# me433.net
KiCad netlist of a schematic drawn in EAGLE
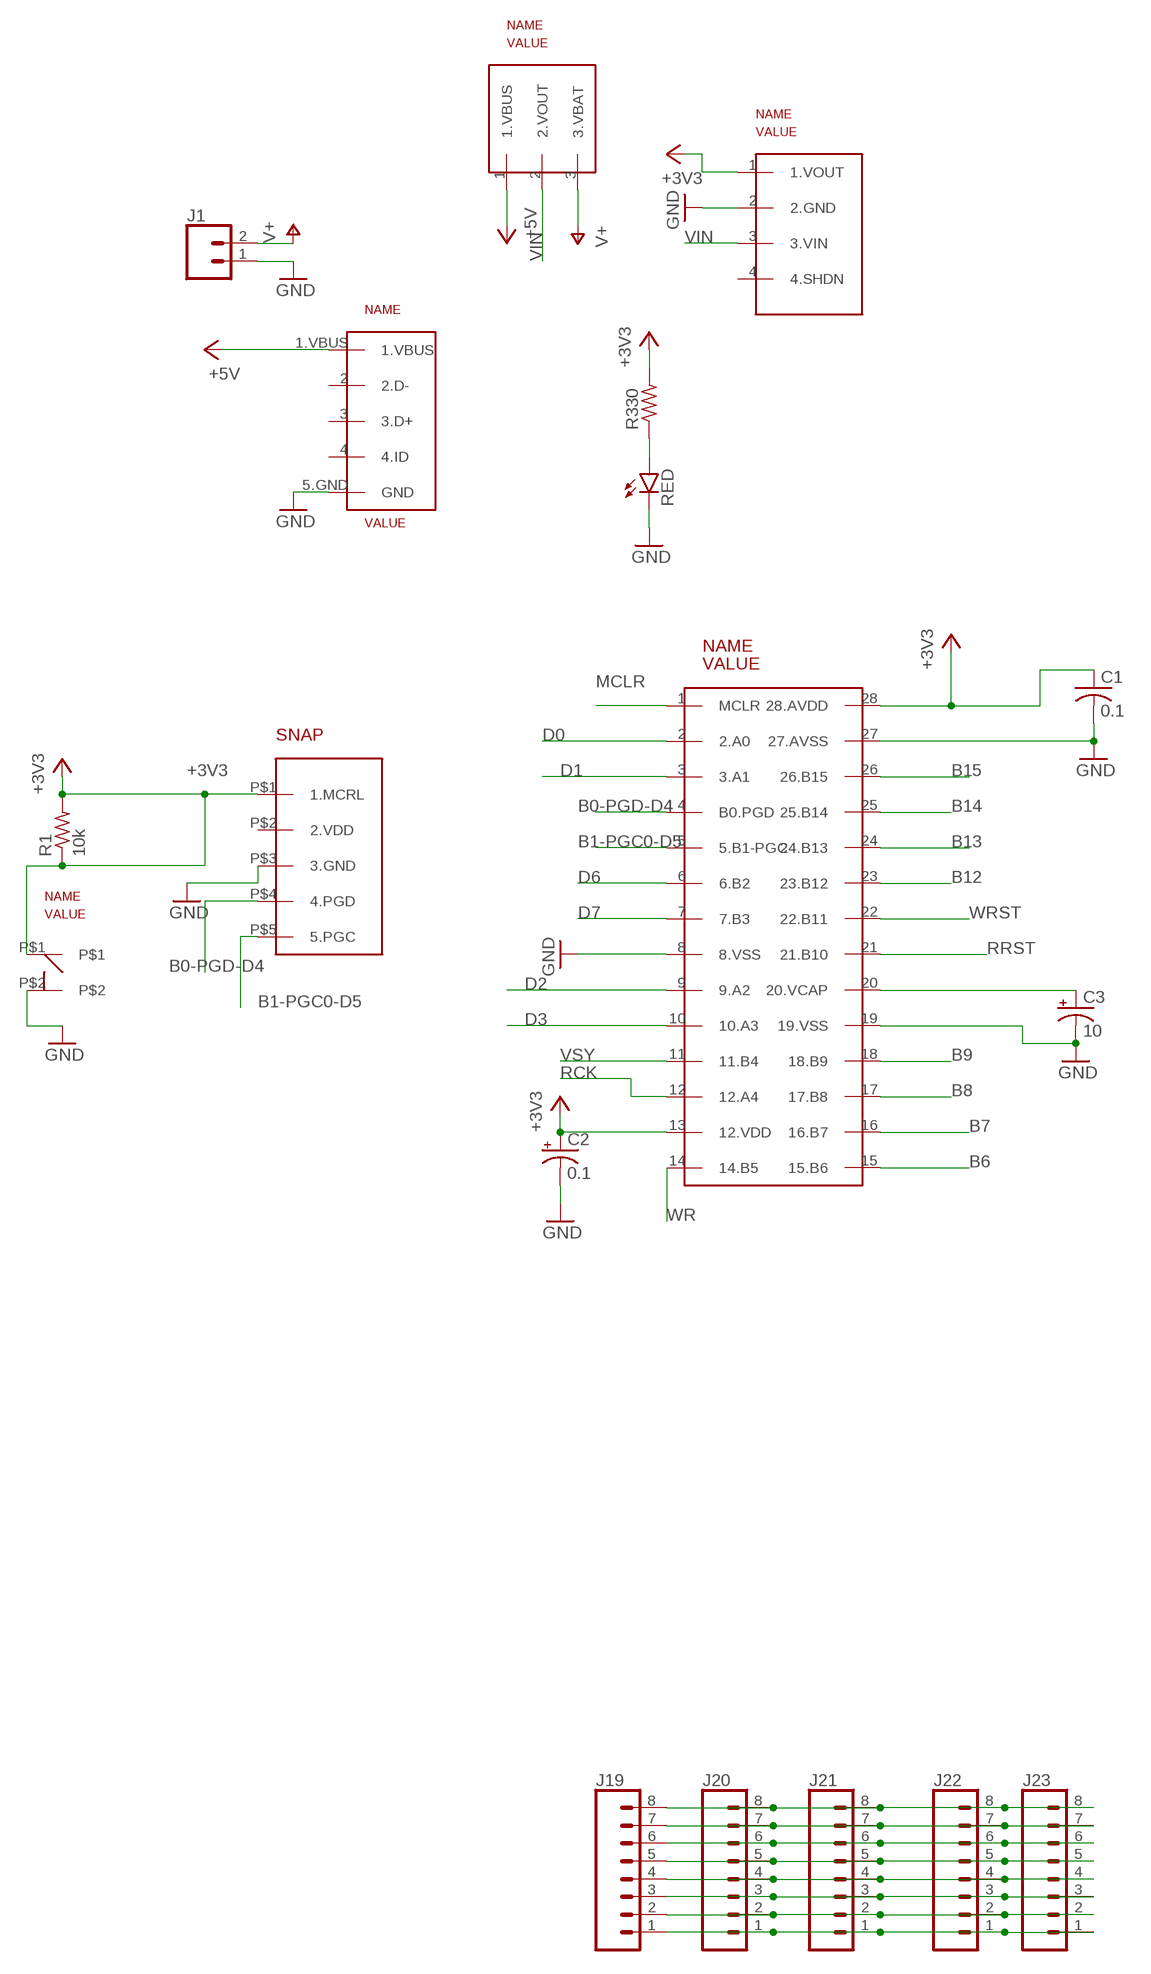
[diagram p0: schematic, sheet 1, part 1 of 2]
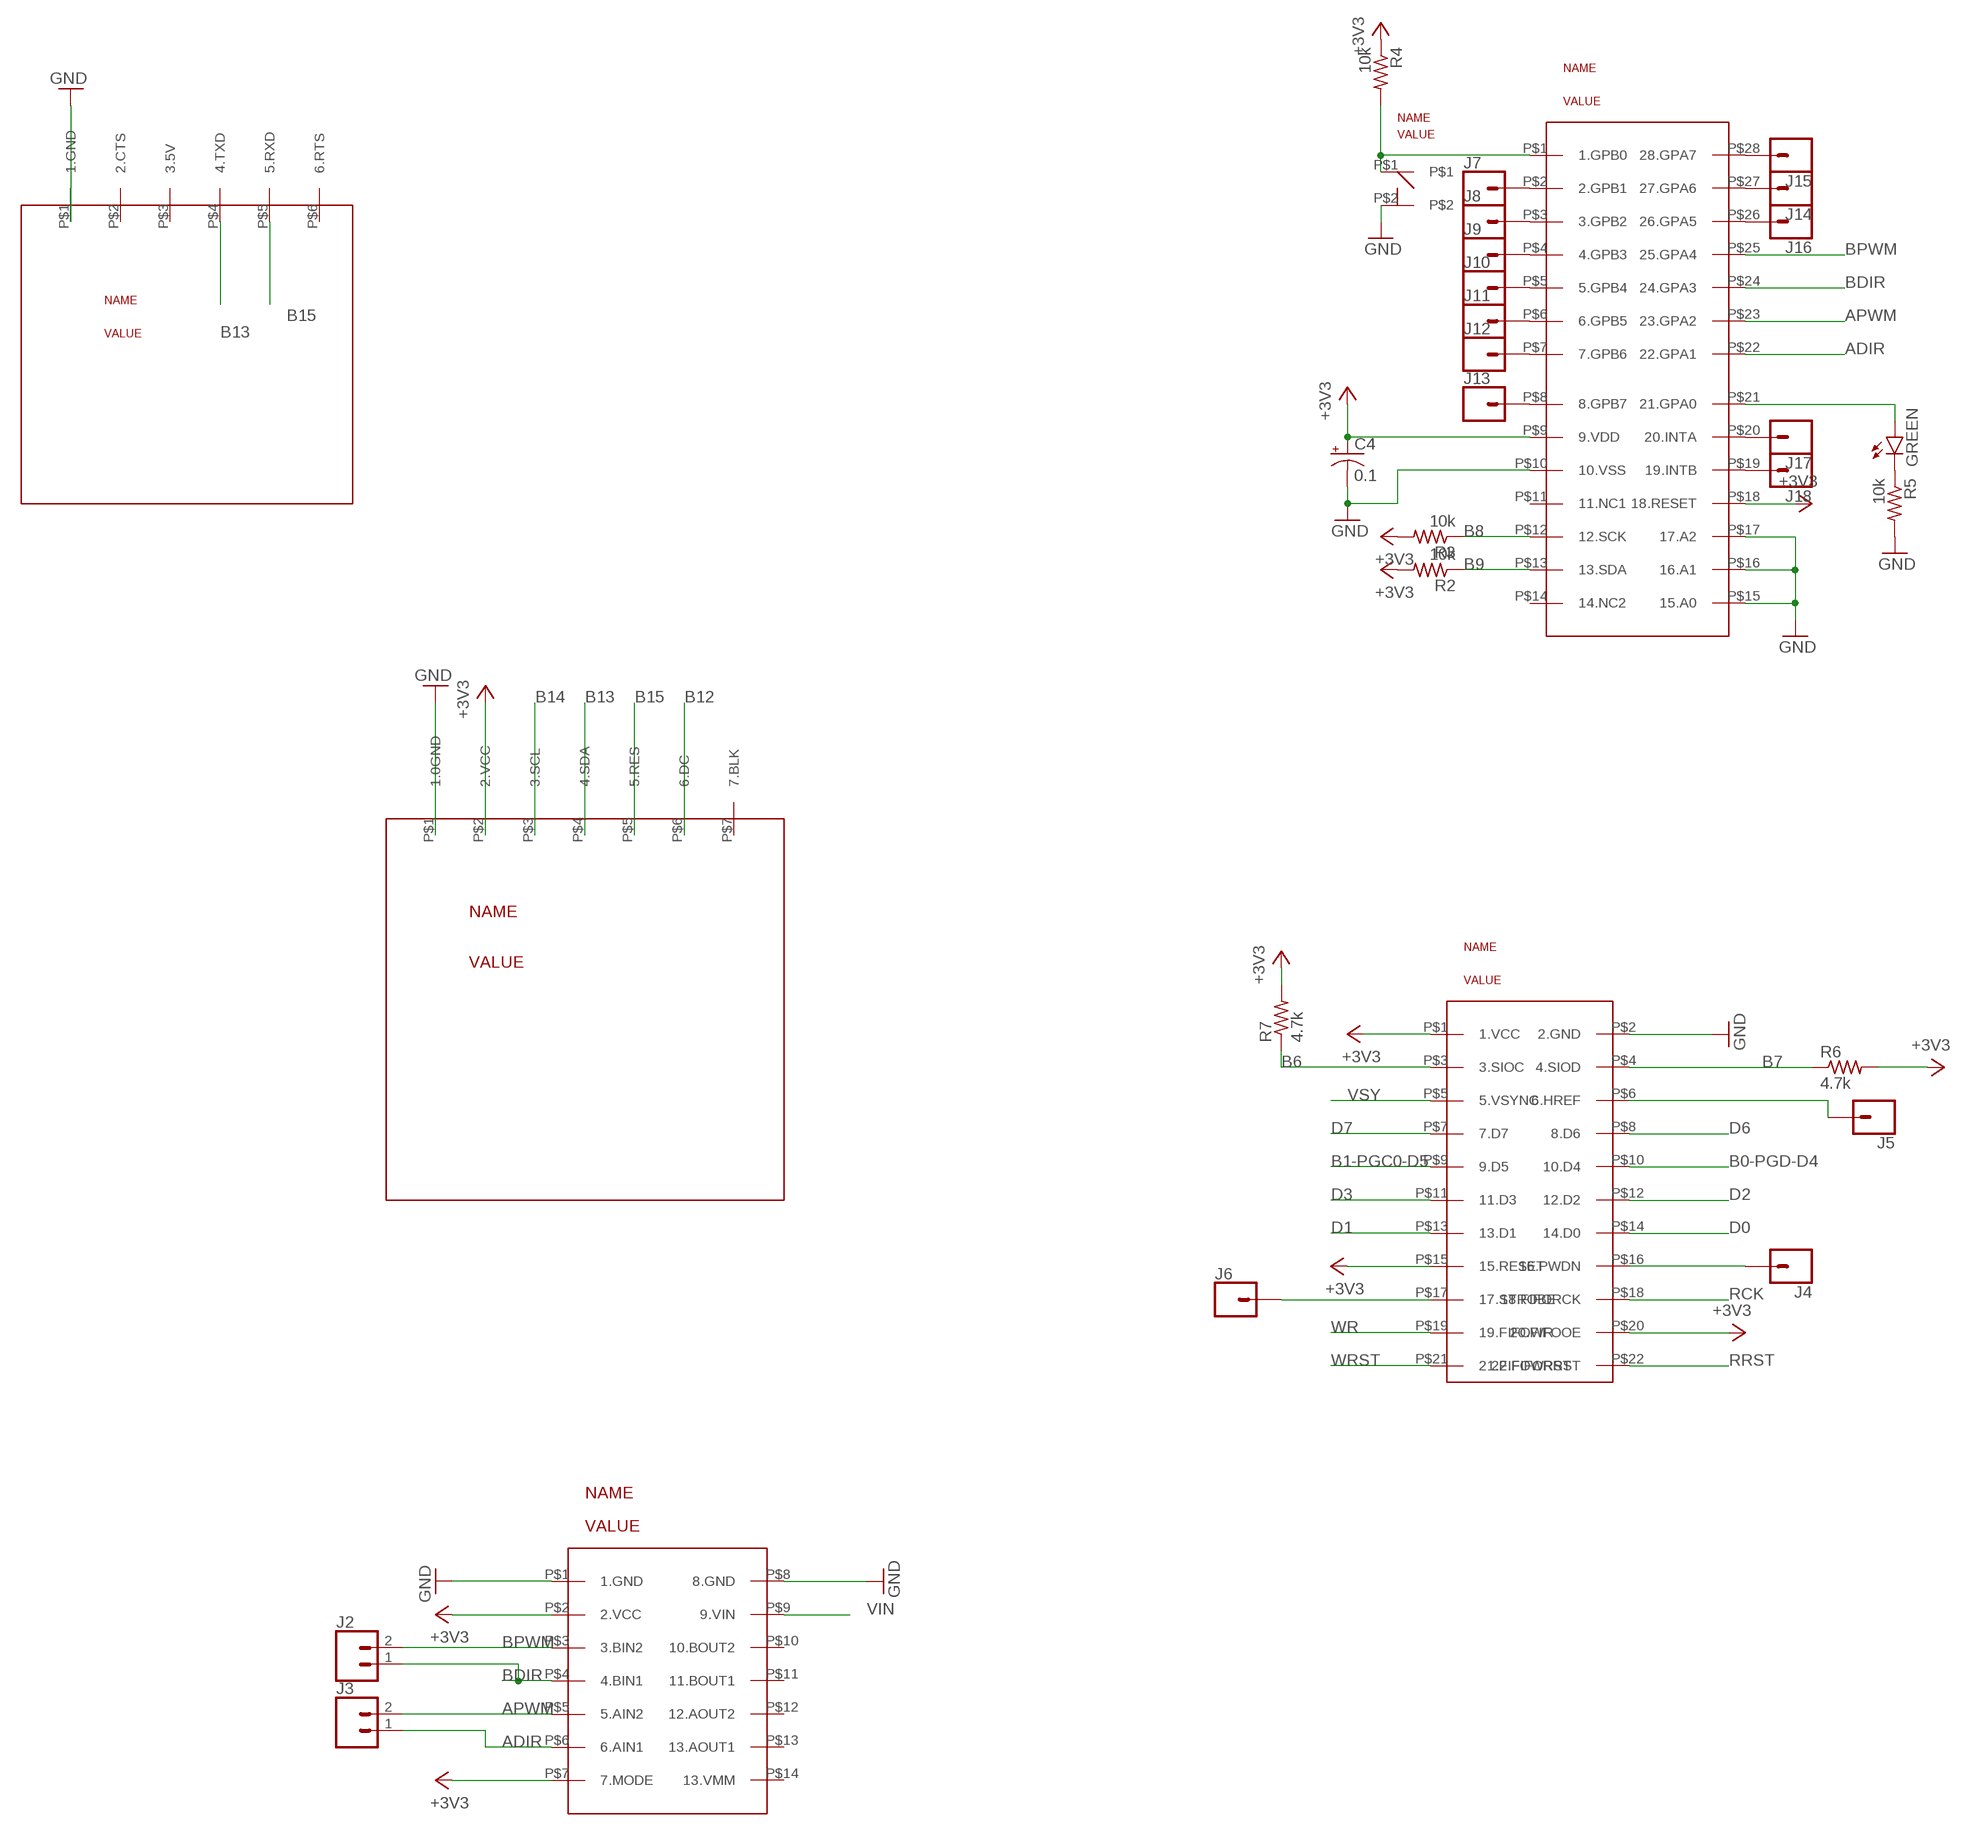
[diagram p1: schematic, sheet 1, part 2 of 2]

(export (version "E")
  (design (tool "Eeschema 10.0.6"))
  (components
    (comp (ref "C1")
      (value "0.1")
      (footprint "eagle-import:C025-030X050")
      (libsource (lib "eagle-import") (part "C-US025-030X050"))
    )
    (comp (ref "C2")
      (value "0.1")
      (footprint "eagle-import:B45181C")
      (libsource (lib "eagle-import") (part "CPOL-USB45181C"))
    )
    (comp (ref "C3")
      (value "10")
      (footprint "eagle-import:B45181C")
      (libsource (lib "eagle-import") (part "CPOL-USB45181C"))
    )
    (comp (ref "C4")
      (value "0.1")
      (footprint "eagle-import:B45181C")
      (libsource (lib "eagle-import") (part "CPOL-USB45181C"))
    )
    (comp (ref "GREEN")
      (value "LED3MM")
      (footprint "eagle-import:LED3MM")
      (libsource (lib "eagle-import") (part "LED3MM"))
    )
    (comp (ref "HBRIDGE")
      (value "H_BRIDGE")
      (footprint "eagle-import:H_BRIDGE")
      (libsource (lib "eagle-import") (part "H_BRIDGE"))
    )
    (comp (ref "J1")
      (value "CONN_02")
      (footprint "eagle-import:1X02")
      (libsource (lib "eagle-import") (part "CONN_02"))
    )
    (comp (ref "J2")
      (value "CONN_02")
      (footprint "eagle-import:1X02")
      (libsource (lib "eagle-import") (part "CONN_02"))
    )
    (comp (ref "J3")
      (value "CONN_02")
      (footprint "eagle-import:1X02")
      (libsource (lib "eagle-import") (part "CONN_02"))
    )
    (comp (ref "J4")
      (value "CONN_01")
      (footprint "eagle-import:1X01")
      (libsource (lib "eagle-import") (part "CONN_01"))
    )
    (comp (ref "J5")
      (value "CONN_01")
      (footprint "eagle-import:1X01")
      (libsource (lib "eagle-import") (part "CONN_01"))
    )
    (comp (ref "J6")
      (value "CONN_01")
      (footprint "eagle-import:1X01")
      (libsource (lib "eagle-import") (part "CONN_01"))
    )
    (comp (ref "J7")
      (value "CONN_01")
      (footprint "eagle-import:1X01")
      (libsource (lib "eagle-import") (part "CONN_01"))
    )
    (comp (ref "J8")
      (value "CONN_01")
      (footprint "eagle-import:1X01")
      (libsource (lib "eagle-import") (part "CONN_01"))
    )
    (comp (ref "J9")
      (value "CONN_01")
      (footprint "eagle-import:1X01")
      (libsource (lib "eagle-import") (part "CONN_01"))
    )
    (comp (ref "J10")
      (value "CONN_01")
      (footprint "eagle-import:1X01")
      (libsource (lib "eagle-import") (part "CONN_01"))
    )
    (comp (ref "J11")
      (value "CONN_01")
      (footprint "eagle-import:1X01")
      (libsource (lib "eagle-import") (part "CONN_01"))
    )
    (comp (ref "J12")
      (value "CONN_01")
      (footprint "eagle-import:1X01")
      (libsource (lib "eagle-import") (part "CONN_01"))
    )
    (comp (ref "J13")
      (value "CONN_01")
      (footprint "eagle-import:1X01")
      (libsource (lib "eagle-import") (part "CONN_01"))
    )
    (comp (ref "J14")
      (value "CONN_01")
      (footprint "eagle-import:1X01")
      (libsource (lib "eagle-import") (part "CONN_01"))
    )
    (comp (ref "J15")
      (value "CONN_01")
      (footprint "eagle-import:1X01")
      (libsource (lib "eagle-import") (part "CONN_01"))
    )
    (comp (ref "J16")
      (value "CONN_01")
      (footprint "eagle-import:1X01")
      (libsource (lib "eagle-import") (part "CONN_01"))
    )
    (comp (ref "J17")
      (value "CONN_01")
      (footprint "eagle-import:1X01")
      (libsource (lib "eagle-import") (part "CONN_01"))
    )
    (comp (ref "J18")
      (value "CONN_01")
      (footprint "eagle-import:1X01")
      (libsource (lib "eagle-import") (part "CONN_01"))
    )
    (comp (ref "J19")
      (value "CONN_08\"")
      (footprint "eagle-import:1X08")
      (libsource (lib "eagle-import") (part "CONN_08{dblquote}"))
    )
    (comp (ref "J20")
      (value "CONN_08\"")
      (footprint "eagle-import:1X08")
      (libsource (lib "eagle-import") (part "CONN_08{dblquote}"))
    )
    (comp (ref "J21")
      (value "CONN_08\"")
      (footprint "eagle-import:1X08")
      (libsource (lib "eagle-import") (part "CONN_08{dblquote}"))
    )
    (comp (ref "J22")
      (value "CONN_08\"")
      (footprint "eagle-import:1X08")
      (libsource (lib "eagle-import") (part "CONN_08{dblquote}"))
    )
    (comp (ref "J23")
      (value "CONN_08\"")
      (footprint "eagle-import:1X08")
      (libsource (lib "eagle-import") (part "CONN_08{dblquote}"))
    )
    (comp (ref "R1")
      (value "10k")
      (footprint "eagle-import:0207_10")
      (libsource (lib "eagle-import") (part "R-US_0207/10"))
    )
    (comp (ref "R2")
      (value "10k")
      (footprint "eagle-import:0207_10")
      (libsource (lib "eagle-import") (part "R-US_0207/10"))
    )
    (comp (ref "R3")
      (value "10k")
      (footprint "eagle-import:0207_10")
      (libsource (lib "eagle-import") (part "R-US_0207/10"))
    )
    (comp (ref "R4")
      (value "10k")
      (footprint "eagle-import:0207_10")
      (libsource (lib "eagle-import") (part "R-US_0207/10"))
    )
    (comp (ref "R5")
      (value "10k")
      (footprint "eagle-import:0207_10")
      (libsource (lib "eagle-import") (part "R-US_0207/10"))
    )
    (comp (ref "R6")
      (value "4.7k")
      (footprint "eagle-import:0207_10")
      (libsource (lib "eagle-import") (part "R-US_0207/10"))
    )
    (comp (ref "R7")
      (value "4.7k")
      (footprint "eagle-import:0207_10")
      (libsource (lib "eagle-import") (part "R-US_0207/10"))
    )
    (comp (ref "R330")
      (value "R-US_0207/10")
      (footprint "eagle-import:0207_10")
      (libsource (lib "eagle-import") (part "R-US_0207/10"))
    )
    (comp (ref "RED")
      (value "LED3MM")
      (footprint "eagle-import:LED3MM")
      (libsource (lib "eagle-import") (part "LED3MM"))
    )
    (comp (ref "RESET")
      (value "PUSH")
      (footprint "eagle-import:PUSH")
      (libsource (lib "eagle-import") (part "PUSH"))
    )
    (comp (ref "U$1")
      (value "PIC32")
      (footprint "eagle-import:DIL28-3")
      (libsource (lib "eagle-import") (part "PIC32"))
    )
    (comp (ref "U$2")
      (value "MICROUSB")
      (footprint "eagle-import:MICROUSB")
      (libsource (lib "eagle-import") (part "MICROUSB"))
    )
    (comp (ref "U$3")
      (value "POLULU3V3")
      (footprint "eagle-import:POLOLU3V3")
      (libsource (lib "eagle-import") (part "POLULU3V3"))
    )
    (comp (ref "U$4")
      (value "SLIDE")
      (footprint "eagle-import:SLIDE")
      (libsource (lib "eagle-import") (part "SLIDE"))
    )
    (comp (ref "U$5")
      (value "FIFO_CAMERA")
      (footprint "eagle-import:FIFO_CAMERA")
      (libsource (lib "eagle-import") (part "FIFO_CAMERA"))
    )
    (comp (ref "U$6")
      (value "SNAP")
      (footprint "eagle-import:SNAP")
      (libsource (lib "eagle-import") (part "SNAP"))
    )
    (comp (ref "U$7")
      (value "USB_CON")
      (footprint "eagle-import:USB_CON")
      (libsource (lib "eagle-import") (part "USB_CON"))
    )
    (comp (ref "U$8")
      (value "LCD")
      (footprint "eagle-import:LCD")
      (libsource (lib "eagle-import") (part "LCD"))
    )
    (comp (ref "U$10")
      (value "EXPANDER")
      (footprint "eagle-import:EXPANDER")
      (libsource (lib "eagle-import") (part "EXPANDER"))
    )
    (comp (ref "USER")
      (value "PUSH")
      (footprint "eagle-import:PUSH")
      (libsource (lib "eagle-import") (part "PUSH"))
    )
  )
  (nets
    (net (code "1") (name "+3V3") (class "Default")
      (node (ref "C1") (pin "1") (pinfunction "1_1") (pintype "passive"))
      (node (ref "C2") (pin "+") (pinfunction "+_+") (pintype "passive"))
      (node (ref "C4") (pin "+") (pinfunction "+_+") (pintype "passive"))
      (node (ref "HBRIDGE") (pin "P$2") (pinfunction "2.VCC_P$2") (pintype "bidirectional"))
      (node (ref "HBRIDGE") (pin "P$7") (pinfunction "7.MODE_P$7") (pintype "bidirectional"))
      (node (ref "R1") (pin "1") (pinfunction "1_1") (pintype "passive"))
      (node (ref "R1") (pin "2") (pinfunction "2_2") (pintype "passive"))
      (node (ref "R2") (pin "2") (pinfunction "2_2") (pintype "passive"))
      (node (ref "R3") (pin "2") (pinfunction "2_2") (pintype "passive"))
      (node (ref "R330") (pin "2") (pinfunction "2_2") (pintype "passive"))
      (node (ref "R4") (pin "1") (pinfunction "1_1") (pintype "passive"))
      (node (ref "R6") (pin "2") (pinfunction "2_2") (pintype "passive"))
      (node (ref "R7") (pin "2") (pinfunction "2_2") (pintype "passive"))
      (node (ref "RESET") (pin "P$1") (pinfunction "P$1_P$1") (pintype "bidirectional"))
      (node (ref "U$1") (pin "13") (pinfunction "12.VDD_13") (pintype "bidirectional"))
      (node (ref "U$1") (pin "28") (pinfunction "28.AVDD_28") (pintype "bidirectional"))
      (node (ref "U$10") (pin "P$18") (pinfunction "18.RESET_P$18") (pintype "bidirectional"))
      (node (ref "U$10") (pin "P$9") (pinfunction "9.VDD_P$9") (pintype "bidirectional"))
      (node (ref "U$3") (pin "1") (pinfunction "1.VOUT_1") (pintype "bidirectional"))
      (node (ref "U$5") (pin "P$1") (pinfunction "1.VCC_P$1") (pintype "bidirectional"))
      (node (ref "U$5") (pin "P$15") (pinfunction "15.RESET_P$15") (pintype "bidirectional"))
      (node (ref "U$5") (pin "P$20") (pinfunction "20.FIFOOE_P$20") (pintype "bidirectional"))
      (node (ref "U$6") (pin "P$1") (pinfunction "1.MCRL_P$1") (pintype "bidirectional"))
      (node (ref "U$8") (pin "P$2") (pinfunction "2.VCC_P$2") (pintype "bidirectional"))
    )
    (net (code "2") (name "+5V") (class "Default")
      (node (ref "U$2") (pin "1.VBUS") (pinfunction "1.VBUS_1.VBUS") (pintype "bidirectional"))
      (node (ref "U$4") (pin "1") (pinfunction "1.VBUS_1") (pintype "bidirectional"))
    )
    (net (code "3") (name "/ADIR") (class "Default")
      (node (ref "HBRIDGE") (pin "P$6") (pinfunction "6.AIN1_P$6") (pintype "bidirectional"))
      (node (ref "J3") (pin "1") (pinfunction "1_1") (pintype "passive"))
      (node (ref "U$10") (pin "P$22") (pinfunction "22.GPA1_P$22") (pintype "bidirectional"))
    )
    (net (code "4") (name "/APWM") (class "Default")
      (node (ref "HBRIDGE") (pin "P$5") (pinfunction "5.AIN2_P$5") (pintype "bidirectional"))
      (node (ref "J3") (pin "2") (pinfunction "2_2") (pintype "passive"))
      (node (ref "U$10") (pin "P$23") (pinfunction "23.GPA2_P$23") (pintype "bidirectional"))
    )
    (net (code "5") (name "/B0-PGD-D4") (class "Default")
      (node (ref "U$1") (pin "4") (pinfunction "B0.PGD_4") (pintype "bidirectional"))
      (node (ref "U$5") (pin "P$10") (pinfunction "10.D4_P$10") (pintype "bidirectional"))
      (node (ref "U$6") (pin "P$4") (pinfunction "4.PGD_P$4") (pintype "bidirectional"))
    )
    (net (code "6") (name "/B1-PGC0-D5") (class "Default")
      (node (ref "U$1") (pin "5") (pinfunction "5.B1-PGC_5") (pintype "bidirectional"))
      (node (ref "U$5") (pin "P$9") (pinfunction "9.D5_P$9") (pintype "bidirectional"))
      (node (ref "U$6") (pin "P$5") (pinfunction "5.PGC_P$5") (pintype "bidirectional"))
    )
    (net (code "7") (name "/B6") (class "Default")
      (node (ref "R7") (pin "1") (pinfunction "1_1") (pintype "passive"))
      (node (ref "U$1") (pin "15") (pinfunction "15.B6_15") (pintype "bidirectional"))
      (node (ref "U$5") (pin "P$3") (pinfunction "3.SIOC_P$3") (pintype "bidirectional"))
    )
    (net (code "8") (name "/B7") (class "Default")
      (node (ref "R6") (pin "1") (pinfunction "1_1") (pintype "passive"))
      (node (ref "U$1") (pin "16") (pinfunction "16.B7_16") (pintype "bidirectional"))
      (node (ref "U$5") (pin "P$4") (pinfunction "4.SIOD_P$4") (pintype "bidirectional"))
    )
    (net (code "9") (name "/B8") (class "Default")
      (node (ref "R3") (pin "1") (pinfunction "1_1") (pintype "passive"))
      (node (ref "U$1") (pin "17") (pinfunction "17.B8_17") (pintype "bidirectional"))
      (node (ref "U$10") (pin "P$12") (pinfunction "12.SCK_P$12") (pintype "bidirectional"))
    )
    (net (code "10") (name "/B9") (class "Default")
      (node (ref "R2") (pin "1") (pinfunction "1_1") (pintype "passive"))
      (node (ref "U$1") (pin "18") (pinfunction "18.B9_18") (pintype "bidirectional"))
      (node (ref "U$10") (pin "P$13") (pinfunction "13.SDA_P$13") (pintype "bidirectional"))
    )
    (net (code "11") (name "/B12") (class "Default")
      (node (ref "U$1") (pin "23") (pinfunction "23.B12_23") (pintype "bidirectional"))
      (node (ref "U$8") (pin "P$6") (pinfunction "6.DC_P$6") (pintype "bidirectional"))
    )
    (net (code "12") (name "/B13") (class "Default")
      (node (ref "U$1") (pin "24") (pinfunction "24.B13_24") (pintype "bidirectional"))
      (node (ref "U$7") (pin "P$4") (pinfunction "4.TXD_P$4") (pintype "bidirectional"))
      (node (ref "U$8") (pin "P$4") (pinfunction "4.SDA_P$4") (pintype "bidirectional"))
    )
    (net (code "13") (name "/B14") (class "Default")
      (node (ref "U$1") (pin "25") (pinfunction "25.B14_25") (pintype "bidirectional"))
      (node (ref "U$8") (pin "P$3") (pinfunction "3.SCL_P$3") (pintype "bidirectional"))
    )
    (net (code "14") (name "/B15") (class "Default")
      (node (ref "U$1") (pin "26") (pinfunction "26.B15_26") (pintype "bidirectional"))
      (node (ref "U$7") (pin "P$5") (pinfunction "5.RXD_P$5") (pintype "bidirectional"))
      (node (ref "U$8") (pin "P$5") (pinfunction "5.RES_P$5") (pintype "bidirectional"))
    )
    (net (code "15") (name "/BDIR") (class "Default")
      (node (ref "HBRIDGE") (pin "P$4") (pinfunction "4.BIN1_P$4") (pintype "bidirectional"))
      (node (ref "J2") (pin "1") (pinfunction "1_1") (pintype "passive"))
      (node (ref "U$10") (pin "P$24") (pinfunction "24.GPA3_P$24") (pintype "bidirectional"))
    )
    (net (code "16") (name "/BPWM") (class "Default")
      (node (ref "HBRIDGE") (pin "P$3") (pinfunction "3.BIN2_P$3") (pintype "bidirectional"))
      (node (ref "J2") (pin "2") (pinfunction "2_2") (pintype "passive"))
      (node (ref "U$10") (pin "P$25") (pinfunction "25.GPA4_P$25") (pintype "bidirectional"))
    )
    (net (code "17") (name "/D0") (class "Default")
      (node (ref "U$1") (pin "2") (pinfunction "2.A0_2") (pintype "bidirectional"))
      (node (ref "U$5") (pin "P$14") (pinfunction "14.D0_P$14") (pintype "bidirectional"))
    )
    (net (code "18") (name "/D1") (class "Default")
      (node (ref "U$1") (pin "3") (pinfunction "3.A1_3") (pintype "bidirectional"))
      (node (ref "U$5") (pin "P$13") (pinfunction "13.D1_P$13") (pintype "bidirectional"))
    )
    (net (code "19") (name "/D2") (class "Default")
      (node (ref "U$1") (pin "9") (pinfunction "9.A2_9") (pintype "bidirectional"))
      (node (ref "U$5") (pin "P$12") (pinfunction "12.D2_P$12") (pintype "bidirectional"))
    )
    (net (code "20") (name "/D3") (class "Default")
      (node (ref "U$1") (pin "10") (pinfunction "10.A3_10") (pintype "bidirectional"))
      (node (ref "U$5") (pin "P$11") (pinfunction "11.D3_P$11") (pintype "bidirectional"))
    )
    (net (code "21") (name "/D6") (class "Default")
      (node (ref "U$1") (pin "6") (pinfunction "6.B2_6") (pintype "bidirectional"))
      (node (ref "U$5") (pin "P$8") (pinfunction "8.D6_P$8") (pintype "bidirectional"))
    )
    (net (code "22") (name "/D7") (class "Default")
      (node (ref "U$1") (pin "7") (pinfunction "7.B3_7") (pintype "bidirectional"))
      (node (ref "U$5") (pin "P$7") (pinfunction "7.D7_P$7") (pintype "bidirectional"))
    )
    (net (code "23") (name "/MCLR") (class "Default")
      (node (ref "U$1") (pin "1") (pinfunction "MCLR_1") (pintype "bidirectional"))
    )
    (net (code "24") (name "/RCK") (class "Default")
      (node (ref "U$1") (pin "12") (pinfunction "12.A4_12") (pintype "bidirectional"))
      (node (ref "U$5") (pin "P$18") (pinfunction "18.FIFORCK_P$18") (pintype "bidirectional"))
    )
    (net (code "25") (name "/RRST") (class "Default")
      (node (ref "U$1") (pin "21") (pinfunction "21.B10_21") (pintype "bidirectional"))
      (node (ref "U$5") (pin "P$22") (pinfunction "22.FIFORRST_P$22") (pintype "bidirectional"))
    )
    (net (code "26") (name "/VIN") (class "Default")
      (node (ref "HBRIDGE") (pin "P$9") (pinfunction "9.VIN_P$9") (pintype "bidirectional"))
      (node (ref "U$3") (pin "3") (pinfunction "3.VIN_3") (pintype "bidirectional"))
      (node (ref "U$4") (pin "2") (pinfunction "2.VOUT_2") (pintype "bidirectional"))
    )
    (net (code "27") (name "/VSY") (class "Default")
      (node (ref "U$1") (pin "11") (pinfunction "11.B4_11") (pintype "bidirectional"))
      (node (ref "U$5") (pin "P$5") (pinfunction "5.VSYNC_P$5") (pintype "bidirectional"))
    )
    (net (code "28") (name "/WR") (class "Default")
      (node (ref "U$1") (pin "14") (pinfunction "14.B5_14") (pintype "bidirectional"))
      (node (ref "U$5") (pin "P$19") (pinfunction "19.FIFOWR_P$19") (pintype "bidirectional"))
    )
    (net (code "29") (name "/WRST") (class "Default")
      (node (ref "U$1") (pin "22") (pinfunction "22.B11_22") (pintype "bidirectional"))
      (node (ref "U$5") (pin "P$21") (pinfunction "21.FIFOWRST_P$21") (pintype "bidirectional"))
    )
    (net (code "30") (name "GND") (class "Default")
      (node (ref "C1") (pin "2") (pinfunction "2_2") (pintype "passive"))
      (node (ref "C2") (pin "-") (pinfunction "-_-") (pintype "passive"))
      (node (ref "C3") (pin "-") (pinfunction "-_-") (pintype "passive"))
      (node (ref "C4") (pin "-") (pinfunction "-_-") (pintype "passive"))
      (node (ref "HBRIDGE") (pin "P$1") (pinfunction "1.GND_P$1") (pintype "bidirectional"))
      (node (ref "HBRIDGE") (pin "P$8") (pinfunction "8.GND_P$8") (pintype "bidirectional"))
      (node (ref "J1") (pin "1") (pinfunction "1_1") (pintype "passive"))
      (node (ref "R5") (pin "2") (pinfunction "2_2") (pintype "passive"))
      (node (ref "RED") (pin "K") (pinfunction "C_K") (pintype "passive"))
      (node (ref "RESET") (pin "P$2") (pinfunction "P$2_P$2") (pintype "bidirectional"))
      (node (ref "U$1") (pin "19") (pinfunction "19.VSS_19") (pintype "bidirectional"))
      (node (ref "U$1") (pin "27") (pinfunction "27.AVSS_27") (pintype "bidirectional"))
      (node (ref "U$1") (pin "8") (pinfunction "8.VSS_8") (pintype "bidirectional"))
      (node (ref "U$10") (pin "P$10") (pinfunction "10.VSS_P$10") (pintype "bidirectional"))
      (node (ref "U$10") (pin "P$15") (pinfunction "15.A0_P$15") (pintype "bidirectional"))
      (node (ref "U$10") (pin "P$16") (pinfunction "16.A1_P$16") (pintype "bidirectional"))
      (node (ref "U$10") (pin "P$17") (pinfunction "17.A2_P$17") (pintype "bidirectional"))
      (node (ref "U$2") (pin "5.GND") (pinfunction "GND_5.GND") (pintype "bidirectional"))
      (node (ref "U$3") (pin "2") (pinfunction "2.GND_2") (pintype "bidirectional"))
      (node (ref "U$5") (pin "P$2") (pinfunction "2.GND_P$2") (pintype "bidirectional"))
      (node (ref "U$6") (pin "P$3") (pinfunction "3.GND_P$3") (pintype "bidirectional"))
      (node (ref "U$7") (pin "P$1") (pinfunction "1.GND_P$1") (pintype "bidirectional"))
      (node (ref "U$8") (pin "P$1") (pinfunction "1.0GND_P$1") (pintype "bidirectional"))
      (node (ref "USER") (pin "P$2") (pinfunction "P$2_P$2") (pintype "bidirectional"))
    )
    (net (code "31") (name "Net-(GREEN-C)") (class "Default")
      (node (ref "GREEN") (pin "K") (pinfunction "C_K") (pintype "passive"))
      (node (ref "R5") (pin "1") (pinfunction "1_1") (pintype "passive"))
    )
    (net (code "32") (name "Net-(J19-Pad1)") (class "Default")
      (node (ref "J19") (pin "1") (pinfunction "1_1") (pintype "passive"))
      (node (ref "J20") (pin "1") (pinfunction "1_1") (pintype "passive"))
      (node (ref "J21") (pin "1") (pinfunction "1_1") (pintype "passive"))
      (node (ref "J22") (pin "1") (pinfunction "1_1") (pintype "passive"))
      (node (ref "J23") (pin "1") (pinfunction "1_1") (pintype "passive"))
    )
    (net (code "33") (name "Net-(J19-Pad2)") (class "Default")
      (node (ref "J19") (pin "2") (pinfunction "2_2") (pintype "passive"))
      (node (ref "J20") (pin "2") (pinfunction "2_2") (pintype "passive"))
      (node (ref "J21") (pin "2") (pinfunction "2_2") (pintype "passive"))
      (node (ref "J22") (pin "2") (pinfunction "2_2") (pintype "passive"))
      (node (ref "J23") (pin "2") (pinfunction "2_2") (pintype "passive"))
    )
    (net (code "34") (name "Net-(J19-Pad3)") (class "Default")
      (node (ref "J19") (pin "3") (pinfunction "3_3") (pintype "passive"))
      (node (ref "J20") (pin "3") (pinfunction "3_3") (pintype "passive"))
      (node (ref "J21") (pin "3") (pinfunction "3_3") (pintype "passive"))
      (node (ref "J22") (pin "3") (pinfunction "3_3") (pintype "passive"))
      (node (ref "J23") (pin "3") (pinfunction "3_3") (pintype "passive"))
    )
    (net (code "35") (name "Net-(J19-Pad4)") (class "Default")
      (node (ref "J19") (pin "4") (pinfunction "4_4") (pintype "passive"))
      (node (ref "J20") (pin "4") (pinfunction "4_4") (pintype "passive"))
      (node (ref "J21") (pin "4") (pinfunction "4_4") (pintype "passive"))
      (node (ref "J22") (pin "4") (pinfunction "4_4") (pintype "passive"))
      (node (ref "J23") (pin "4") (pinfunction "4_4") (pintype "passive"))
    )
    (net (code "36") (name "Net-(J19-Pad5)") (class "Default")
      (node (ref "J19") (pin "5") (pinfunction "5_5") (pintype "passive"))
      (node (ref "J20") (pin "5") (pinfunction "5_5") (pintype "passive"))
      (node (ref "J21") (pin "5") (pinfunction "5_5") (pintype "passive"))
      (node (ref "J22") (pin "5") (pinfunction "5_5") (pintype "passive"))
      (node (ref "J23") (pin "5") (pinfunction "5_5") (pintype "passive"))
    )
    (net (code "37") (name "Net-(J19-Pad6)") (class "Default")
      (node (ref "J19") (pin "6") (pinfunction "6_6") (pintype "passive"))
      (node (ref "J20") (pin "6") (pinfunction "6_6") (pintype "passive"))
      (node (ref "J21") (pin "6") (pinfunction "6_6") (pintype "passive"))
      (node (ref "J22") (pin "6") (pinfunction "6_6") (pintype "passive"))
      (node (ref "J23") (pin "6") (pinfunction "6_6") (pintype "passive"))
    )
    (net (code "38") (name "Net-(J19-Pad7)") (class "Default")
      (node (ref "J19") (pin "7") (pinfunction "7_7") (pintype "passive"))
      (node (ref "J20") (pin "7") (pinfunction "7_7") (pintype "passive"))
      (node (ref "J21") (pin "7") (pinfunction "7_7") (pintype "passive"))
      (node (ref "J22") (pin "7") (pinfunction "7_7") (pintype "passive"))
      (node (ref "J23") (pin "7") (pinfunction "7_7") (pintype "passive"))
    )
    (net (code "39") (name "Net-(J19-Pad8)") (class "Default")
      (node (ref "J19") (pin "8") (pinfunction "8_8") (pintype "passive"))
      (node (ref "J20") (pin "8") (pinfunction "8_8") (pintype "passive"))
      (node (ref "J21") (pin "8") (pinfunction "8_8") (pintype "passive"))
      (node (ref "J22") (pin "8") (pinfunction "8_8") (pintype "passive"))
      (node (ref "J23") (pin "8") (pinfunction "8_8") (pintype "passive"))
    )
    (net (code "40") (name "Net-(R330-Pad1)") (class "Default")
      (node (ref "R330") (pin "1") (pinfunction "1_1") (pintype "passive"))
      (node (ref "RED") (pin "A") (pinfunction "A_A") (pintype "passive"))
    )
    (net (code "41") (name "Net-(U$1-20.VCAP)") (class "Default")
      (node (ref "C3") (pin "+") (pinfunction "+_+") (pintype "passive"))
      (node (ref "U$1") (pin "20") (pinfunction "20.VCAP_20") (pintype "bidirectional"))
    )
    (net (code "42") (name "Net-(U$5-6.HREF)") (class "Default")
      (node (ref "J5") (pin "1") (pinfunction "1_1") (pintype "passive"))
      (node (ref "U$5") (pin "P$6") (pinfunction "6.HREF_P$6") (pintype "bidirectional"))
    )
    (net (code "43") (name "Net-(U$5-16.PWDN)") (class "Default")
      (node (ref "J4") (pin "1") (pinfunction "1_1") (pintype "passive"))
      (node (ref "U$5") (pin "P$16") (pinfunction "16.PWDN_P$16") (pintype "bidirectional"))
    )
    (net (code "44") (name "Net-(U$5-17.STROBE)") (class "Default")
      (node (ref "J6") (pin "1") (pinfunction "1_1") (pintype "passive"))
      (node (ref "U$5") (pin "P$17") (pinfunction "17.STROBE_P$17") (pintype "bidirectional"))
    )
    (net (code "45") (name "Net-(U$10-1.GPB0)") (class "Default")
      (node (ref "R4") (pin "2") (pinfunction "2_2") (pintype "passive"))
      (node (ref "U$10") (pin "P$1") (pinfunction "1.GPB0_P$1") (pintype "bidirectional"))
      (node (ref "USER") (pin "P$1") (pinfunction "P$1_P$1") (pintype "bidirectional"))
    )
    (net (code "46") (name "Net-(U$10-2.GPB1)") (class "Default")
      (node (ref "J7") (pin "1") (pinfunction "1_1") (pintype "passive"))
      (node (ref "U$10") (pin "P$2") (pinfunction "2.GPB1_P$2") (pintype "bidirectional"))
    )
    (net (code "47") (name "Net-(U$10-3.GPB2)") (class "Default")
      (node (ref "J8") (pin "1") (pinfunction "1_1") (pintype "passive"))
      (node (ref "U$10") (pin "P$3") (pinfunction "3.GPB2_P$3") (pintype "bidirectional"))
    )
    (net (code "48") (name "Net-(U$10-4.GPB3)") (class "Default")
      (node (ref "J9") (pin "1") (pinfunction "1_1") (pintype "passive"))
      (node (ref "U$10") (pin "P$4") (pinfunction "4.GPB3_P$4") (pintype "bidirectional"))
    )
    (net (code "49") (name "Net-(U$10-5.GPB4)") (class "Default")
      (node (ref "J10") (pin "1") (pinfunction "1_1") (pintype "passive"))
      (node (ref "U$10") (pin "P$5") (pinfunction "5.GPB4_P$5") (pintype "bidirectional"))
    )
    (net (code "50") (name "Net-(U$10-6.GPB5)") (class "Default")
      (node (ref "J11") (pin "1") (pinfunction "1_1") (pintype "passive"))
      (node (ref "U$10") (pin "P$6") (pinfunction "6.GPB5_P$6") (pintype "bidirectional"))
    )
    (net (code "51") (name "Net-(U$10-7.GPB6)") (class "Default")
      (node (ref "J12") (pin "1") (pinfunction "1_1") (pintype "passive"))
      (node (ref "U$10") (pin "P$7") (pinfunction "7.GPB6_P$7") (pintype "bidirectional"))
    )
    (net (code "52") (name "Net-(U$10-8.GPB7)") (class "Default")
      (node (ref "J13") (pin "1") (pinfunction "1_1") (pintype "passive"))
      (node (ref "U$10") (pin "P$8") (pinfunction "8.GPB7_P$8") (pintype "bidirectional"))
    )
    (net (code "53") (name "Net-(U$10-19.INTB)") (class "Default")
      (node (ref "J18") (pin "1") (pinfunction "1_1") (pintype "passive"))
      (node (ref "U$10") (pin "P$19") (pinfunction "19.INTB_P$19") (pintype "bidirectional"))
    )
    (net (code "54") (name "Net-(U$10-20.INTA)") (class "Default")
      (node (ref "J17") (pin "1") (pinfunction "1_1") (pintype "passive"))
      (node (ref "U$10") (pin "P$20") (pinfunction "20.INTA_P$20") (pintype "bidirectional"))
    )
    (net (code "55") (name "Net-(U$10-21.GPA0)") (class "Default")
      (node (ref "GREEN") (pin "A") (pinfunction "A_A") (pintype "passive"))
      (node (ref "U$10") (pin "P$21") (pinfunction "21.GPA0_P$21") (pintype "bidirectional"))
    )
    (net (code "56") (name "Net-(U$10-26.GPA5)") (class "Default")
      (node (ref "J16") (pin "1") (pinfunction "1_1") (pintype "passive"))
      (node (ref "U$10") (pin "P$26") (pinfunction "26.GPA5_P$26") (pintype "bidirectional"))
    )
    (net (code "57") (name "Net-(U$10-27.GPA6)") (class "Default")
      (node (ref "J14") (pin "1") (pinfunction "1_1") (pintype "passive"))
      (node (ref "U$10") (pin "P$27") (pinfunction "27.GPA6_P$27") (pintype "bidirectional"))
    )
    (net (code "58") (name "Net-(U$10-28.GPA7)") (class "Default")
      (node (ref "J15") (pin "1") (pinfunction "1_1") (pintype "passive"))
      (node (ref "U$10") (pin "P$28") (pinfunction "28.GPA7_P$28") (pintype "bidirectional"))
    )
    (net (code "59") (name "V+") (class "Default")
      (node (ref "J1") (pin "2") (pinfunction "2_2") (pintype "passive"))
      (node (ref "U$4") (pin "3") (pinfunction "3.VBAT_3") (pintype "bidirectional"))
    )
    (net (code "60") (name "unconnected-(HBRIDGE-10.BOUT2-PadP$10)") (class "Default")
      (node (ref "HBRIDGE") (pin "P$10") (pinfunction "10.BOUT2_P$10") (pintype "bidirectional"))
    )
    (net (code "61") (name "unconnected-(HBRIDGE-11.BOUT1-PadP$11)") (class "Default")
      (node (ref "HBRIDGE") (pin "P$11") (pinfunction "11.BOUT1_P$11") (pintype "bidirectional"))
    )
    (net (code "62") (name "unconnected-(HBRIDGE-12.AOUT2-PadP$12)") (class "Default")
      (node (ref "HBRIDGE") (pin "P$12") (pinfunction "12.AOUT2_P$12") (pintype "bidirectional"))
    )
    (net (code "63") (name "unconnected-(HBRIDGE-13.AOUT1-PadP$13)") (class "Default")
      (node (ref "HBRIDGE") (pin "P$13") (pinfunction "13.AOUT1_P$13") (pintype "bidirectional"))
    )
    (net (code "64") (name "unconnected-(HBRIDGE-13.VMM-PadP$14)") (class "Default")
      (node (ref "HBRIDGE") (pin "P$14") (pinfunction "13.VMM_P$14") (pintype "bidirectional"))
    )
    (net (code "65") (name "unconnected-(U$2-2.D--Pad2)") (class "Default")
      (node (ref "U$2") (pin "2") (pinfunction "2.D-_2") (pintype "bidirectional"))
    )
    (net (code "66") (name "unconnected-(U$2-3.D+-Pad3)") (class "Default")
      (node (ref "U$2") (pin "3") (pinfunction "3.D+_3") (pintype "bidirectional"))
    )
    (net (code "67") (name "unconnected-(U$2-4.ID-Pad4)") (class "Default")
      (node (ref "U$2") (pin "4") (pinfunction "4.ID_4") (pintype "bidirectional"))
    )
    (net (code "68") (name "unconnected-(U$3-4.SHDN-Pad4)") (class "Default")
      (node (ref "U$3") (pin "4") (pinfunction "4.SHDN_4") (pintype "bidirectional"))
    )
    (net (code "69") (name "unconnected-(U$6-2.VDD-PadP$2)") (class "Default")
      (node (ref "U$6") (pin "P$2") (pinfunction "2.VDD_P$2") (pintype "bidirectional"))
    )
    (net (code "70") (name "unconnected-(U$7-2.CTS-PadP$2)") (class "Default")
      (node (ref "U$7") (pin "P$2") (pinfunction "2.CTS_P$2") (pintype "bidirectional"))
    )
    (net (code "71") (name "unconnected-(U$7-3.5V-PadP$3)") (class "Default")
      (node (ref "U$7") (pin "P$3") (pinfunction "3.5V_P$3") (pintype "bidirectional"))
    )
    (net (code "72") (name "unconnected-(U$7-6.RTS-PadP$6)") (class "Default")
      (node (ref "U$7") (pin "P$6") (pinfunction "6.RTS_P$6") (pintype "bidirectional"))
    )
    (net (code "73") (name "unconnected-(U$8-7.BLK-PadP$7)") (class "Default")
      (node (ref "U$8") (pin "P$7") (pinfunction "7.BLK_P$7") (pintype "bidirectional"))
    )
    (net (code "74") (name "unconnected-(U$10-11.NC1-PadP$11)") (class "Default")
      (node (ref "U$10") (pin "P$11") (pinfunction "11.NC1_P$11") (pintype "bidirectional"))
    )
    (net (code "75") (name "unconnected-(U$10-14.NC2-PadP$14)") (class "Default")
      (node (ref "U$10") (pin "P$14") (pinfunction "14.NC2_P$14") (pintype "bidirectional"))
    )
  )
)
